# FPGA.net
KiCad netlist of a schematic drawn in Altium Designer
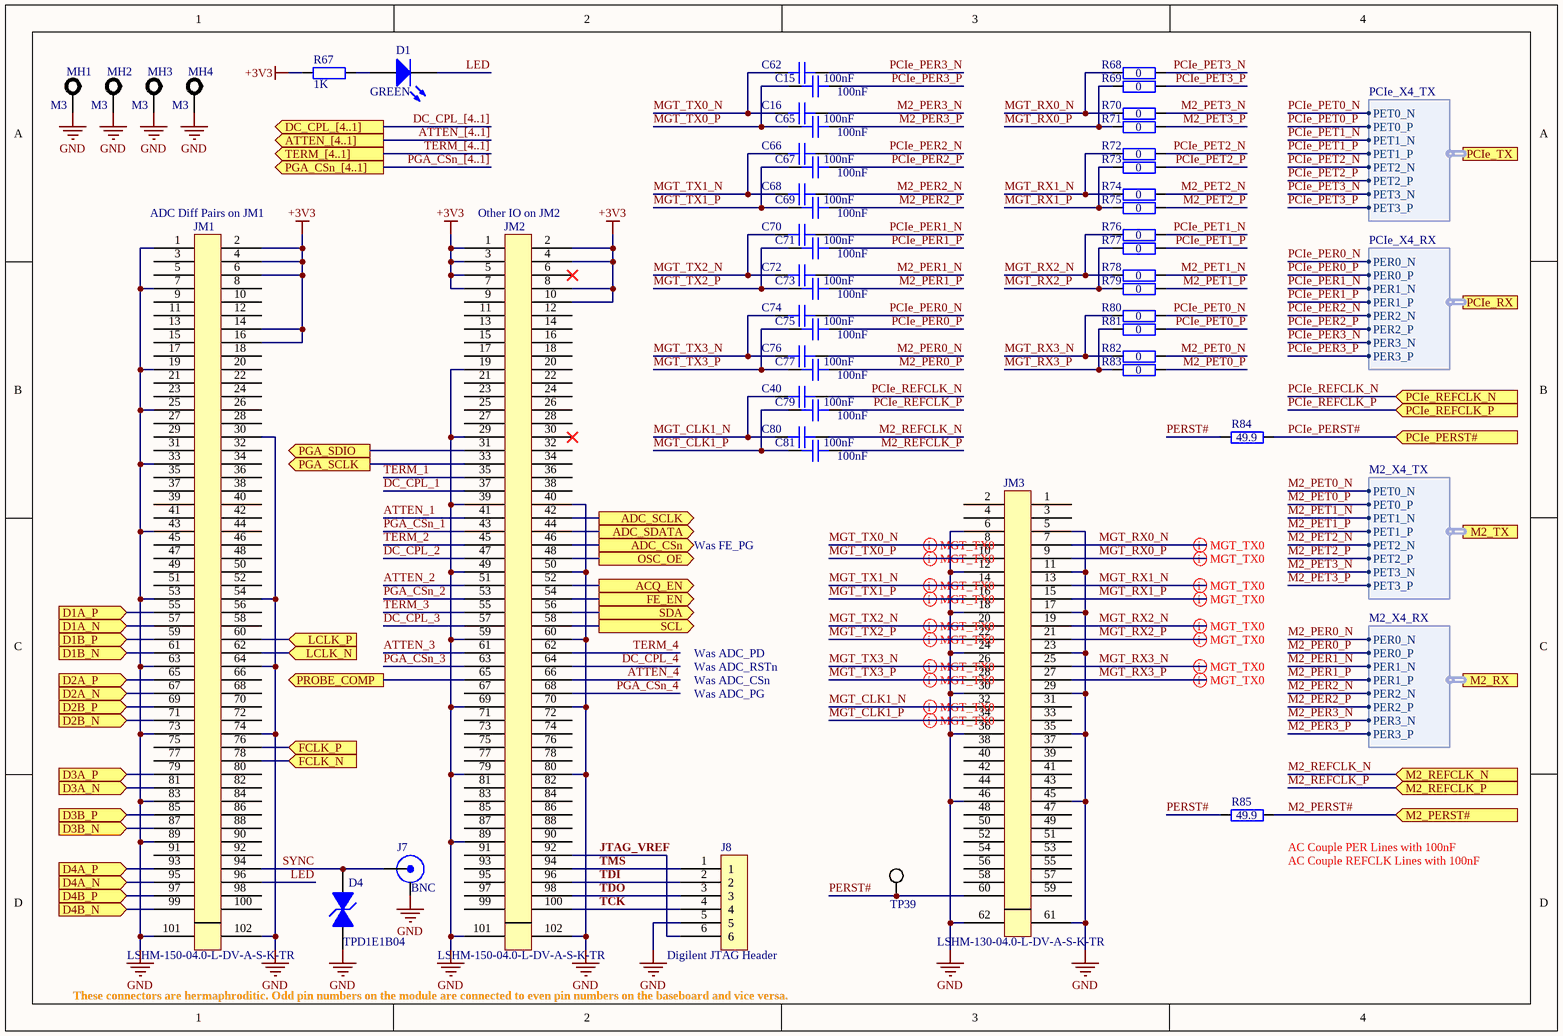
[diagram p0: FPGA.SchDoc]

(export (version "E")
  (design (tool "Eeschema 10.0.6"))
  (components
    (comp (ref "C15")
      (value "100nF")
      (footprint "GEN_C_0201")
      (libsource (lib "DSO") (part "CAP 100nF 6.3V X5R 0201"))
    )
    (comp (ref "C16")
      (value "100nF")
      (footprint "GEN_C_0201")
      (libsource (lib "DSO") (part "CAP 100nF 6.3V X5R 0201"))
    )
    (comp (ref "C40")
      (value "100nF")
      (footprint "GEN_C_0201")
      (libsource (lib "DSO") (part "CAP 100nF 6.3V X5R 0201"))
    )
    (comp (ref "C62")
      (value "100nF")
      (footprint "GEN_C_0201")
      (libsource (lib "DSO") (part "CAP 100nF 6.3V X5R 0201"))
    )
    (comp (ref "C65")
      (value "100nF")
      (footprint "GEN_C_0201")
      (libsource (lib "DSO") (part "CAP 100nF 6.3V X5R 0201"))
    )
    (comp (ref "C66")
      (value "100nF")
      (footprint "GEN_C_0201")
      (libsource (lib "DSO") (part "CAP 100nF 6.3V X5R 0201"))
    )
    (comp (ref "C67")
      (value "100nF")
      (footprint "GEN_C_0201")
      (libsource (lib "DSO") (part "CAP 100nF 6.3V X5R 0201"))
    )
    (comp (ref "C68")
      (value "100nF")
      (footprint "GEN_C_0201")
      (libsource (lib "DSO") (part "CAP 100nF 6.3V X5R 0201"))
    )
    (comp (ref "C69")
      (value "100nF")
      (footprint "GEN_C_0201")
      (libsource (lib "DSO") (part "CAP 100nF 6.3V X5R 0201"))
    )
    (comp (ref "C70")
      (value "100nF")
      (footprint "GEN_C_0201")
      (libsource (lib "DSO") (part "CAP 100nF 6.3V X5R 0201"))
    )
    (comp (ref "C71")
      (value "100nF")
      (footprint "GEN_C_0201")
      (libsource (lib "DSO") (part "CAP 100nF 6.3V X5R 0201"))
    )
    (comp (ref "C72")
      (value "100nF")
      (footprint "GEN_C_0201")
      (libsource (lib "DSO") (part "CAP 100nF 6.3V X5R 0201"))
    )
    (comp (ref "C73")
      (value "100nF")
      (footprint "GEN_C_0201")
      (libsource (lib "DSO") (part "CAP 100nF 6.3V X5R 0201"))
    )
    (comp (ref "C74")
      (value "100nF")
      (footprint "GEN_C_0201")
      (libsource (lib "DSO") (part "CAP 100nF 6.3V X5R 0201"))
    )
    (comp (ref "C75")
      (value "100nF")
      (footprint "GEN_C_0201")
      (libsource (lib "DSO") (part "CAP 100nF 6.3V X5R 0201"))
    )
    (comp (ref "C76")
      (value "100nF")
      (footprint "GEN_C_0201")
      (libsource (lib "DSO") (part "CAP 100nF 6.3V X5R 0201"))
    )
    (comp (ref "C77")
      (value "100nF")
      (footprint "GEN_C_0201")
      (libsource (lib "DSO") (part "CAP 100nF 6.3V X5R 0201"))
    )
    (comp (ref "C79")
      (value "100nF")
      (footprint "GEN_C_0201")
      (libsource (lib "DSO") (part "CAP 100nF 6.3V X5R 0201"))
    )
    (comp (ref "C80")
      (value "100nF")
      (footprint "GEN_C_0201")
      (libsource (lib "DSO") (part "CAP 100nF 6.3V X5R 0201"))
    )
    (comp (ref "C81")
      (value "100nF")
      (footprint "GEN_C_0201")
      (libsource (lib "DSO") (part "CAP 100nF 6.3V X5R 0201"))
    )
    (comp (ref "D1")
      (value "GREEN")
      (footprint "LED_0603_LTST-S270K")
      (libsource (lib "DSO") (part "LED GREEN 0603 LTST-S270K"))
    )
    (comp (ref "D4")
      (value "TPD1E1B04")
      (footprint "TI_X1SON_DPY0002A")
      (libsource (lib "DSO") (part "TVS TPD1E1B04"))
    )
    (comp (ref "J7") (value "BNC") (footprint "MOL_0731000105") (libsource (lib "DSO") (part "BNC JACK R/A")))
    (comp (ref "J8")
      (value "2.54mm 6 Pin TH")
      (footprint "GEN_2.54mm_6_Pin_TH_RA")
      (libsource (lib "DSO") (part "CONN 2.54mm 6 Pin TH RA"))
    )
    (comp (ref "JM1")
      (value "LSHM-150-04.0-L-DV-A-S-K-TR")
      (footprint "SAM_LSHM-150-XX.X-XX-DV-A-S")
      (libsource (lib "DSO") (part "CONN LSHM-150-04.0-L-DV-A-S-K-TR"))
    )
    (comp (ref "JM2")
      (value "LSHM-150-04.0-L-DV-A-S-K-TR")
      (footprint "SAM_LSHM-150-XX.X-XX-DV-A-S")
      (libsource (lib "DSO") (part "CONN LSHM-150-04.0-L-DV-A-S-K-TR"))
    )
    (comp (ref "JM3")
      (value "LSHM-130-04.0-L-DV-A-S-K-TR")
      (footprint "SAM_LSHM-130-XX.X-XX-DV-A-S")
      (libsource (lib "DSO") (part "CONN LSHM-130-04.0-L-DV-A-S-K-TR"))
    )
    (comp (ref "MH1") (value "M3") (footprint "MH M3") (libsource (lib "DSO") (part "MH M3")))
    (comp (ref "MH2") (value "M3") (footprint "MH M3") (libsource (lib "DSO") (part "MH M3")))
    (comp (ref "MH3") (value "M3") (footprint "MH M3") (libsource (lib "DSO") (part "MH M3")))
    (comp (ref "MH4") (value "M3") (footprint "MH M3") (libsource (lib "DSO") (part "MH M3")))
    (comp (ref "R67")
      (value "1K")
      (footprint "GEN_R_0402")
      (fields (field (name "TOLERANCE") "1%"))
      (libsource (lib "DSO") (part "RES 1K OHM 1% 1/10W 0402"))
    )
    (comp (ref "R68")
      (value "0")
      (footprint "GEN_R_0201")
      (fields (field (name "TOLERANCE") "1%"))
      (libsource (lib "DSO") (part "RES 0 OHM 1% 1/20W 0201"))
    )
    (comp (ref "R69")
      (value "0")
      (footprint "GEN_R_0201")
      (fields (field (name "TOLERANCE") "1%"))
      (libsource (lib "DSO") (part "RES 0 OHM 1% 1/20W 0201"))
    )
    (comp (ref "R70")
      (value "0")
      (footprint "GEN_R_0201")
      (fields (field (name "TOLERANCE") "1%"))
      (libsource (lib "DSO") (part "RES 0 OHM 1% 1/20W 0201"))
    )
    (comp (ref "R71")
      (value "0")
      (footprint "GEN_R_0201")
      (fields (field (name "TOLERANCE") "1%"))
      (libsource (lib "DSO") (part "RES 0 OHM 1% 1/20W 0201"))
    )
    (comp (ref "R72")
      (value "0")
      (footprint "GEN_R_0201")
      (fields (field (name "TOLERANCE") "1%"))
      (libsource (lib "DSO") (part "RES 0 OHM 1% 1/20W 0201"))
    )
    (comp (ref "R73")
      (value "0")
      (footprint "GEN_R_0201")
      (fields (field (name "TOLERANCE") "1%"))
      (libsource (lib "DSO") (part "RES 0 OHM 1% 1/20W 0201"))
    )
    (comp (ref "R74")
      (value "0")
      (footprint "GEN_R_0201")
      (fields (field (name "TOLERANCE") "1%"))
      (libsource (lib "DSO") (part "RES 0 OHM 1% 1/20W 0201"))
    )
    (comp (ref "R75")
      (value "0")
      (footprint "GEN_R_0201")
      (fields (field (name "TOLERANCE") "1%"))
      (libsource (lib "DSO") (part "RES 0 OHM 1% 1/20W 0201"))
    )
    (comp (ref "R76")
      (value "0")
      (footprint "GEN_R_0201")
      (fields (field (name "TOLERANCE") "1%"))
      (libsource (lib "DSO") (part "RES 0 OHM 1% 1/20W 0201"))
    )
    (comp (ref "R77")
      (value "0")
      (footprint "GEN_R_0201")
      (fields (field (name "TOLERANCE") "1%"))
      (libsource (lib "DSO") (part "RES 0 OHM 1% 1/20W 0201"))
    )
    (comp (ref "R78")
      (value "0")
      (footprint "GEN_R_0201")
      (fields (field (name "TOLERANCE") "1%"))
      (libsource (lib "DSO") (part "RES 0 OHM 1% 1/20W 0201"))
    )
    (comp (ref "R79")
      (value "0")
      (footprint "GEN_R_0201")
      (fields (field (name "TOLERANCE") "1%"))
      (libsource (lib "DSO") (part "RES 0 OHM 1% 1/20W 0201"))
    )
    (comp (ref "R80")
      (value "0")
      (footprint "GEN_R_0201")
      (fields (field (name "TOLERANCE") "1%"))
      (libsource (lib "DSO") (part "RES 0 OHM 1% 1/20W 0201"))
    )
    (comp (ref "R81")
      (value "0")
      (footprint "GEN_R_0201")
      (fields (field (name "TOLERANCE") "1%"))
      (libsource (lib "DSO") (part "RES 0 OHM 1% 1/20W 0201"))
    )
    (comp (ref "R82")
      (value "0")
      (footprint "GEN_R_0201")
      (fields (field (name "TOLERANCE") "1%"))
      (libsource (lib "DSO") (part "RES 0 OHM 1% 1/20W 0201"))
    )
    (comp (ref "R83")
      (value "0")
      (footprint "GEN_R_0201")
      (fields (field (name "TOLERANCE") "1%"))
      (libsource (lib "DSO") (part "RES 0 OHM 1% 1/20W 0201"))
    )
    (comp (ref "R84")
      (value "49.9")
      (footprint "GEN_R_0402")
      (fields (field (name "TOLERANCE") "1%"))
      (libsource (lib "DSO") (part "RES 49.9 OHM 1% 1/10W 0402"))
    )
    (comp (ref "R85")
      (value "49.9")
      (footprint "GEN_R_0402")
      (fields (field (name "TOLERANCE") "1%"))
      (libsource (lib "DSO") (part "RES 49.9 OHM 1% 1/10W 0402"))
    )
    (comp (ref "TP39") (value "PCB") (footprint "GEN_TP_PCB") (libsource (lib "DSO") (part "TP PCB 1mm")))
  )
  (nets
    (net (code "5") (name "+3V3") (class "Default")
      (node (ref "JM1") (pin "14") (pinfunction "14_14") (pintype "passive"))
      (node (ref "JM1") (pin "16") (pinfunction "16_16") (pintype "passive"))
      (node (ref "JM1") (pin "2") (pinfunction "2_2") (pintype "passive"))
      (node (ref "JM1") (pin "4") (pinfunction "4_4") (pintype "passive"))
      (node (ref "JM1") (pin "6") (pinfunction "6_6") (pintype "passive"))
      (node (ref "JM2") (pin "1") (pinfunction "1_1") (pintype "passive"))
      (node (ref "JM2") (pin "10") (pinfunction "10_10") (pintype "passive"))
      (node (ref "JM2") (pin "2") (pinfunction "2_2") (pintype "passive"))
      (node (ref "JM2") (pin "3") (pinfunction "3_3") (pintype "passive"))
      (node (ref "JM2") (pin "4") (pinfunction "4_4") (pintype "passive"))
      (node (ref "JM2") (pin "5") (pinfunction "5_5") (pintype "passive"))
      (node (ref "JM2") (pin "7") (pinfunction "7_7") (pintype "passive"))
      (node (ref "JM2") (pin "8") (pinfunction "8_8") (pintype "passive"))
      (node (ref "R67") (pin "2") (pinfunction "2_2") (pintype "passive"))
    )
    (net (code "6") (name "/ACQ_EN") (class "Default")
      (node (ref "JM2") (pin "52") (pinfunction "52_52") (pintype "passive"))
    )
    (net (code "7") (name "/ADC_CSn") (class "Default")
      (node (ref "JM2") (pin "46") (pinfunction "46_46") (pintype "passive"))
    )
    (net (code "8") (name "/ADC_SCLK") (class "Default")
      (node (ref "JM2") (pin "42") (pinfunction "42_42") (pintype "passive"))
    )
    (net (code "9") (name "/ADC_SDATA") (class "Default")
      (node (ref "JM2") (pin "44") (pinfunction "44_44") (pintype "passive"))
    )
    (net (code "10") (name "/ATTEN_1") (class "Default")
      (node (ref "JM2") (pin "41") (pinfunction "41_41") (pintype "passive"))
    )
    (net (code "11") (name "/ATTEN_2") (class "Default")
      (node (ref "JM2") (pin "51") (pinfunction "51_51") (pintype "passive"))
    )
    (net (code "12") (name "/ATTEN_3") (class "Default")
      (node (ref "JM2") (pin "61") (pinfunction "61_61") (pintype "passive"))
    )
    (net (code "13") (name "/ATTEN_4") (class "Default")
      (node (ref "JM2") (pin "66") (pinfunction "66_66") (pintype "passive"))
    )
    (net (code "15") (name "/D1A_N") (class "Default")
      (node (ref "JM1") (pin "57") (pinfunction "57_57") (pintype "passive"))
    )
    (net (code "16") (name "/D1A_P") (class "Default")
      (node (ref "JM1") (pin "55") (pinfunction "55_55") (pintype "passive"))
    )
    (net (code "17") (name "/D1B_N") (class "Default")
      (node (ref "JM1") (pin "61") (pinfunction "61_61") (pintype "passive"))
    )
    (net (code "18") (name "/D1B_P") (class "Default")
      (node (ref "JM1") (pin "59") (pinfunction "59_59") (pintype "passive"))
    )
    (net (code "19") (name "/D2A_N") (class "Default")
      (node (ref "JM1") (pin "67") (pinfunction "67_67") (pintype "passive"))
    )
    (net (code "20") (name "/D2A_P") (class "Default")
      (node (ref "JM1") (pin "65") (pinfunction "65_65") (pintype "passive"))
    )
    (net (code "21") (name "/D2B_N") (class "Default")
      (node (ref "JM1") (pin "71") (pinfunction "71_71") (pintype "passive"))
    )
    (net (code "22") (name "/D2B_P") (class "Default")
      (node (ref "JM1") (pin "69") (pinfunction "69_69") (pintype "passive"))
    )
    (net (code "23") (name "/D3A_N") (class "Default")
      (node (ref "JM1") (pin "81") (pinfunction "81_81") (pintype "passive"))
    )
    (net (code "24") (name "/D3A_P") (class "Default")
      (node (ref "JM1") (pin "79") (pinfunction "79_79") (pintype "passive"))
    )
    (net (code "25") (name "/D3B_N") (class "Default")
      (node (ref "JM1") (pin "87") (pinfunction "87_87") (pintype "passive"))
    )
    (net (code "26") (name "/D3B_P") (class "Default")
      (node (ref "JM1") (pin "85") (pinfunction "85_85") (pintype "passive"))
    )
    (net (code "27") (name "/D4A_N") (class "Default")
      (node (ref "JM1") (pin "95") (pinfunction "95_95") (pintype "passive"))
    )
    (net (code "28") (name "/D4A_P") (class "Default")
      (node (ref "JM1") (pin "93") (pinfunction "93_93") (pintype "passive"))
    )
    (net (code "29") (name "/D4B_N") (class "Default")
      (node (ref "JM1") (pin "99") (pinfunction "99_99") (pintype "passive"))
    )
    (net (code "30") (name "/D4B_P") (class "Default")
      (node (ref "JM1") (pin "97") (pinfunction "97_97") (pintype "passive"))
    )
    (net (code "31") (name "/DC_CPL_1") (class "Default")
      (node (ref "JM2") (pin "37") (pinfunction "37_37") (pintype "passive"))
    )
    (net (code "32") (name "/DC_CPL_2") (class "Default")
      (node (ref "JM2") (pin "47") (pinfunction "47_47") (pintype "passive"))
    )
    (net (code "33") (name "/DC_CPL_3") (class "Default")
      (node (ref "JM2") (pin "57") (pinfunction "57_57") (pintype "passive"))
    )
    (net (code "34") (name "/DC_CPL_4") (class "Default")
      (node (ref "JM2") (pin "64") (pinfunction "64_64") (pintype "passive"))
    )
    (net (code "36") (name "/FCLK_N") (class "Default")
      (node (ref "JM1") (pin "78") (pinfunction "78_78") (pintype "passive"))
    )
    (net (code "37") (name "/FCLK_P") (class "Default")
      (node (ref "JM1") (pin "76") (pinfunction "76_76") (pintype "passive"))
    )
    (net (code "38") (name "/FE_EN") (class "Default")
      (node (ref "JM2") (pin "54") (pinfunction "54_54") (pintype "passive"))
    )
    (net (code "39") (name "/JTAG_VREF") (class "Default")
      (node (ref "J8") (pin "6") (pinfunction "6_6") (pintype "passive"))
      (node (ref "JM2") (pin "92") (pinfunction "92_92") (pintype "passive"))
    )
    (net (code "40") (name "/LCLK_N") (class "Default")
      (node (ref "JM1") (pin "62") (pinfunction "62_62") (pintype "passive"))
    )
    (net (code "41") (name "/LCLK_P") (class "Default")
      (node (ref "JM1") (pin "60") (pinfunction "60_60") (pintype "passive"))
    )
    (net (code "42") (name "/LED") (class "Default")
      (node (ref "D1") (pin "1") (pinfunction "K_1") (pintype "passive"))
      (node (ref "JM1") (pin "96") (pinfunction "96_96") (pintype "passive"))
    )
    (net (code "43") (name "/M2_PER0_N") (class "Default")
      (node (ref "C76") (pin "1") (pinfunction "1_1") (pintype "passive"))
    )
    (net (code "44") (name "/M2_PER0_P") (class "Default")
      (node (ref "C77") (pin "1") (pinfunction "1_1") (pintype "passive"))
    )
    (net (code "45") (name "/M2_PER1_N") (class "Default")
      (node (ref "C72") (pin "1") (pinfunction "1_1") (pintype "passive"))
    )
    (net (code "46") (name "/M2_PER1_P") (class "Default")
      (node (ref "C73") (pin "1") (pinfunction "1_1") (pintype "passive"))
    )
    (net (code "47") (name "/M2_PER2_N") (class "Default")
      (node (ref "C68") (pin "1") (pinfunction "1_1") (pintype "passive"))
    )
    (net (code "48") (name "/M2_PER2_P") (class "Default")
      (node (ref "C69") (pin "1") (pinfunction "1_1") (pintype "passive"))
    )
    (net (code "49") (name "/M2_PER3_N") (class "Default")
      (node (ref "C16") (pin "1") (pinfunction "1_1") (pintype "passive"))
    )
    (net (code "50") (name "/M2_PER3_P") (class "Default")
      (node (ref "C65") (pin "1") (pinfunction "1_1") (pintype "passive"))
    )
    (net (code "51") (name "/M2_PERST#") (class "Default")
      (node (ref "R85") (pin "2") (pinfunction "2_2") (pintype "passive"))
    )
    (net (code "52") (name "/M2_PET0_N") (class "Default")
      (node (ref "R82") (pin "2") (pinfunction "2_2") (pintype "passive"))
    )
    (net (code "53") (name "/M2_PET0_P") (class "Default")
      (node (ref "R83") (pin "2") (pinfunction "2_2") (pintype "passive"))
    )
    (net (code "54") (name "/M2_PET1_N") (class "Default")
      (node (ref "R78") (pin "2") (pinfunction "2_2") (pintype "passive"))
    )
    (net (code "55") (name "/M2_PET1_P") (class "Default")
      (node (ref "R79") (pin "2") (pinfunction "2_2") (pintype "passive"))
    )
    (net (code "56") (name "/M2_PET2_N") (class "Default")
      (node (ref "R74") (pin "2") (pinfunction "2_2") (pintype "passive"))
    )
    (net (code "57") (name "/M2_PET2_P") (class "Default")
      (node (ref "R75") (pin "2") (pinfunction "2_2") (pintype "passive"))
    )
    (net (code "58") (name "/M2_PET3_N") (class "Default")
      (node (ref "R70") (pin "2") (pinfunction "2_2") (pintype "passive"))
    )
    (net (code "59") (name "/M2_PET3_P") (class "Default")
      (node (ref "R71") (pin "2") (pinfunction "2_2") (pintype "passive"))
    )
    (net (code "60") (name "/M2_REFCLK_N") (class "Default")
      (node (ref "C80") (pin "1") (pinfunction "1_1") (pintype "passive"))
    )
    (net (code "61") (name "/M2_REFCLK_P") (class "Default")
      (node (ref "C81") (pin "1") (pinfunction "1_1") (pintype "passive"))
    )
    (net (code "62") (name "/MGT_CLK1_N") (class "Default")
      (node (ref "C40") (pin "2") (pinfunction "2_2") (pintype "passive"))
      (node (ref "C80") (pin "2") (pinfunction "2_2") (pintype "passive"))
      (node (ref "JM3") (pin "32") (pinfunction "32_32") (pintype "passive"))
    )
    (net (code "63") (name "/MGT_CLK1_P") (class "Default")
      (node (ref "C79") (pin "2") (pinfunction "2_2") (pintype "passive"))
      (node (ref "C81") (pin "2") (pinfunction "2_2") (pintype "passive"))
      (node (ref "JM3") (pin "34") (pinfunction "34_34") (pintype "passive"))
    )
    (net (code "64") (name "/MGT_RX0_N") (class "Default")
      (node (ref "JM3") (pin "7") (pinfunction "7_7") (pintype "passive"))
      (node (ref "R68") (pin "1") (pinfunction "1_1") (pintype "passive"))
      (node (ref "R70") (pin "1") (pinfunction "1_1") (pintype "passive"))
    )
    (net (code "65") (name "/MGT_RX0_P") (class "Default")
      (node (ref "JM3") (pin "9") (pinfunction "9_9") (pintype "passive"))
      (node (ref "R69") (pin "1") (pinfunction "1_1") (pintype "passive"))
      (node (ref "R71") (pin "1") (pinfunction "1_1") (pintype "passive"))
    )
    (net (code "66") (name "/MGT_RX1_N") (class "Default")
      (node (ref "JM3") (pin "13") (pinfunction "13_13") (pintype "passive"))
      (node (ref "R72") (pin "1") (pinfunction "1_1") (pintype "passive"))
      (node (ref "R74") (pin "1") (pinfunction "1_1") (pintype "passive"))
    )
    (net (code "67") (name "/MGT_RX1_P") (class "Default")
      (node (ref "JM3") (pin "15") (pinfunction "15_15") (pintype "passive"))
      (node (ref "R73") (pin "1") (pinfunction "1_1") (pintype "passive"))
      (node (ref "R75") (pin "1") (pinfunction "1_1") (pintype "passive"))
    )
    (net (code "68") (name "/MGT_RX2_N") (class "Default")
      (node (ref "JM3") (pin "19") (pinfunction "19_19") (pintype "passive"))
      (node (ref "R76") (pin "1") (pinfunction "1_1") (pintype "passive"))
      (node (ref "R78") (pin "1") (pinfunction "1_1") (pintype "passive"))
    )
    (net (code "69") (name "/MGT_RX2_P") (class "Default")
      (node (ref "JM3") (pin "21") (pinfunction "21_21") (pintype "passive"))
      (node (ref "R77") (pin "1") (pinfunction "1_1") (pintype "passive"))
      (node (ref "R79") (pin "1") (pinfunction "1_1") (pintype "passive"))
    )
    (net (code "70") (name "/MGT_RX3_N") (class "Default")
      (node (ref "JM3") (pin "25") (pinfunction "25_25") (pintype "passive"))
      (node (ref "R80") (pin "1") (pinfunction "1_1") (pintype "passive"))
      (node (ref "R82") (pin "1") (pinfunction "1_1") (pintype "passive"))
    )
    (net (code "71") (name "/MGT_RX3_P") (class "Default")
      (node (ref "JM3") (pin "27") (pinfunction "27_27") (pintype "passive"))
      (node (ref "R81") (pin "1") (pinfunction "1_1") (pintype "passive"))
      (node (ref "R83") (pin "1") (pinfunction "1_1") (pintype "passive"))
    )
    (net (code "72") (name "/MGT_TX0_N") (class "Default")
      (node (ref "C16") (pin "2") (pinfunction "2_2") (pintype "passive"))
      (node (ref "C62") (pin "2") (pinfunction "2_2") (pintype "passive"))
      (node (ref "JM3") (pin "8") (pinfunction "8_8") (pintype "passive"))
    )
    (net (code "73") (name "/MGT_TX0_P") (class "Default")
      (node (ref "C15") (pin "2") (pinfunction "2_2") (pintype "passive"))
      (node (ref "C65") (pin "2") (pinfunction "2_2") (pintype "passive"))
      (node (ref "JM3") (pin "10") (pinfunction "10_10") (pintype "passive"))
    )
    (net (code "74") (name "/MGT_TX1_N") (class "Default")
      (node (ref "C66") (pin "2") (pinfunction "2_2") (pintype "passive"))
      (node (ref "C68") (pin "2") (pinfunction "2_2") (pintype "passive"))
      (node (ref "JM3") (pin "14") (pinfunction "14_14") (pintype "passive"))
    )
    (net (code "75") (name "/MGT_TX1_P") (class "Default")
      (node (ref "C67") (pin "2") (pinfunction "2_2") (pintype "passive"))
      (node (ref "C69") (pin "2") (pinfunction "2_2") (pintype "passive"))
      (node (ref "JM3") (pin "16") (pinfunction "16_16") (pintype "passive"))
    )
    (net (code "76") (name "/MGT_TX2_N") (class "Default")
      (node (ref "C70") (pin "2") (pinfunction "2_2") (pintype "passive"))
      (node (ref "C72") (pin "2") (pinfunction "2_2") (pintype "passive"))
      (node (ref "JM3") (pin "20") (pinfunction "20_20") (pintype "passive"))
    )
    (net (code "77") (name "/MGT_TX2_P") (class "Default")
      (node (ref "C71") (pin "2") (pinfunction "2_2") (pintype "passive"))
      (node (ref "C73") (pin "2") (pinfunction "2_2") (pintype "passive"))
      (node (ref "JM3") (pin "22") (pinfunction "22_22") (pintype "passive"))
    )
    (net (code "78") (name "/MGT_TX3_N") (class "Default")
      (node (ref "C74") (pin "2") (pinfunction "2_2") (pintype "passive"))
      (node (ref "C76") (pin "2") (pinfunction "2_2") (pintype "passive"))
      (node (ref "JM3") (pin "26") (pinfunction "26_26") (pintype "passive"))
    )
    (net (code "79") (name "/MGT_TX3_P") (class "Default")
      (node (ref "C75") (pin "2") (pinfunction "2_2") (pintype "passive"))
      (node (ref "C77") (pin "2") (pinfunction "2_2") (pintype "passive"))
      (node (ref "JM3") (pin "28") (pinfunction "28_28") (pintype "passive"))
    )
    (net (code "80") (name "/OSC_OE") (class "Default")
      (node (ref "JM2") (pin "48") (pinfunction "48_48") (pintype "passive"))
    )
    (net (code "81") (name "/PCIe_PER0_N") (class "Default")
      (node (ref "C74") (pin "1") (pinfunction "1_1") (pintype "passive"))
    )
    (net (code "82") (name "/PCIe_PER0_P") (class "Default")
      (node (ref "C75") (pin "1") (pinfunction "1_1") (pintype "passive"))
    )
    (net (code "83") (name "/PCIe_PER1_N") (class "Default")
      (node (ref "C70") (pin "1") (pinfunction "1_1") (pintype "passive"))
    )
    (net (code "84") (name "/PCIe_PER1_P") (class "Default")
      (node (ref "C71") (pin "1") (pinfunction "1_1") (pintype "passive"))
    )
    (net (code "85") (name "/PCIe_PER2_N") (class "Default")
      (node (ref "C66") (pin "1") (pinfunction "1_1") (pintype "passive"))
    )
    (net (code "86") (name "/PCIe_PER2_P") (class "Default")
      (node (ref "C67") (pin "1") (pinfunction "1_1") (pintype "passive"))
    )
    (net (code "87") (name "/PCIe_PER3_N") (class "Default")
      (node (ref "C62") (pin "1") (pinfunction "1_1") (pintype "passive"))
    )
    (net (code "88") (name "/PCIe_PER3_P") (class "Default")
      (node (ref "C15") (pin "1") (pinfunction "1_1") (pintype "passive"))
    )
    (net (code "89") (name "/PCIe_PERST#") (class "Default")
      (node (ref "R84") (pin "2") (pinfunction "2_2") (pintype "passive"))
    )
    (net (code "90") (name "/PCIe_PET0_N") (class "Default")
      (node (ref "R80") (pin "2") (pinfunction "2_2") (pintype "passive"))
    )
    (net (code "91") (name "/PCIe_PET0_P") (class "Default")
      (node (ref "R81") (pin "2") (pinfunction "2_2") (pintype "passive"))
    )
    (net (code "92") (name "/PCIe_PET1_N") (class "Default")
      (node (ref "R76") (pin "2") (pinfunction "2_2") (pintype "passive"))
    )
    (net (code "93") (name "/PCIe_PET1_P") (class "Default")
      (node (ref "R77") (pin "2") (pinfunction "2_2") (pintype "passive"))
    )
    (net (code "94") (name "/PCIe_PET2_N") (class "Default")
      (node (ref "R72") (pin "2") (pinfunction "2_2") (pintype "passive"))
    )
    (net (code "95") (name "/PCIe_PET2_P") (class "Default")
      (node (ref "R73") (pin "2") (pinfunction "2_2") (pintype "passive"))
    )
    (net (code "96") (name "/PCIe_PET3_N") (class "Default")
      (node (ref "R68") (pin "2") (pinfunction "2_2") (pintype "passive"))
    )
    (net (code "97") (name "/PCIe_PET3_P") (class "Default")
      (node (ref "R69") (pin "2") (pinfunction "2_2") (pintype "passive"))
    )
    (net (code "98") (name "/PCIe_REFCLK_N") (class "Default")
      (node (ref "C40") (pin "1") (pinfunction "1_1") (pintype "passive"))
    )
    (net (code "99") (name "/PCIe_REFCLK_P") (class "Default")
      (node (ref "C79") (pin "1") (pinfunction "1_1") (pintype "passive"))
    )
    (net (code "100") (name "/PERST#") (class "Default")
      (node (ref "JM3") (pin "60") (pinfunction "60_60") (pintype "passive"))
      (node (ref "R84") (pin "1") (pinfunction "1_1") (pintype "passive"))
      (node (ref "R85") (pin "1") (pinfunction "1_1") (pintype "passive"))
      (node (ref "TP39") (pin "1") (pinfunction "1_1") (pintype "passive"))
    )
    (net (code "101") (name "/PGA_CSn_1") (class "Default")
      (node (ref "JM2") (pin "43") (pinfunction "43_43") (pintype "passive"))
    )
    (net (code "102") (name "/PGA_CSn_2") (class "Default")
      (node (ref "JM2") (pin "53") (pinfunction "53_53") (pintype "passive"))
    )
    (net (code "103") (name "/PGA_CSn_3") (class "Default")
      (node (ref "JM2") (pin "63") (pinfunction "63_63") (pintype "passive"))
    )
    (net (code "104") (name "/PGA_CSn_4") (class "Default")
      (node (ref "JM2") (pin "68") (pinfunction "68_68") (pintype "passive"))
    )
    (net (code "106") (name "/PGA_SCLK") (class "Default")
      (node (ref "JM2") (pin "33") (pinfunction "33_33") (pintype "passive"))
    )
    (net (code "107") (name "/PGA_SDIO") (class "Default")
      (node (ref "JM2") (pin "31") (pinfunction "31_31") (pintype "passive"))
    )
    (net (code "108") (name "/PROBE_COMP") (class "Default")
      (node (ref "JM2") (pin "65") (pinfunction "65_65") (pintype "passive"))
    )
    (net (code "109") (name "/SCL") (class "Default")
      (node (ref "JM2") (pin "58") (pinfunction "58_58") (pintype "passive"))
    )
    (net (code "110") (name "/SDA") (class "Default")
      (node (ref "JM2") (pin "56") (pinfunction "56_56") (pintype "passive"))
    )
    (net (code "111") (name "/SYNC") (class "Default")
      (node (ref "D4") (pin "1") (pinfunction "K_1") (pintype "passive"))
      (node (ref "J7") (pin "1") (pinfunction "Signal_1") (pintype "passive"))
      (node (ref "JM1") (pin "94") (pinfunction "94_94") (pintype "passive"))
    )
    (net (code "112") (name "/TCK") (class "Default")
      (node (ref "J8") (pin "4") (pinfunction "4_4") (pintype "passive"))
      (node (ref "JM2") (pin "100") (pinfunction "100_100") (pintype "passive"))
    )
    (net (code "113") (name "/TDI") (class "Default")
      (node (ref "J8") (pin "2") (pinfunction "2_2") (pintype "passive"))
      (node (ref "JM2") (pin "96") (pinfunction "96_96") (pintype "passive"))
    )
    (net (code "114") (name "/TDO") (class "Default")
      (node (ref "J8") (pin "3") (pinfunction "3_3") (pintype "passive"))
      (node (ref "JM2") (pin "98") (pinfunction "98_98") (pintype "passive"))
    )
    (net (code "115") (name "/TERM_1") (class "Default")
      (node (ref "JM2") (pin "35") (pinfunction "35_35") (pintype "passive"))
    )
    (net (code "116") (name "/TERM_2") (class "Default")
      (node (ref "JM2") (pin "45") (pinfunction "45_45") (pintype "passive"))
    )
    (net (code "117") (name "/TERM_3") (class "Default")
      (node (ref "JM2") (pin "55") (pinfunction "55_55") (pintype "passive"))
    )
    (net (code "118") (name "/TERM_4") (class "Default")
      (node (ref "JM2") (pin "62") (pinfunction "62_62") (pintype "passive"))
    )
    (net (code "120") (name "/TMS") (class "Default")
      (node (ref "J8") (pin "1") (pinfunction "1_1") (pintype "passive"))
      (node (ref "JM2") (pin "94") (pinfunction "94_94") (pintype "passive"))
    )
    (net (code "125") (name "GND") (class "Default")
      (node (ref "D4") (pin "2") (pinfunction "A_2") (pintype "passive"))
      (node (ref "J7") (pin "2") (pinfunction "SHIELD_2") (pintype "passive"))
      (node (ref "J8") (pin "5") (pinfunction "5_5") (pintype "passive"))
      (node (ref "JM1") (pin "1") (pinfunction "1_1") (pintype "passive"))
      (node (ref "JM1") (pin "101") (pinfunction "101_101") (pintype "passive"))
      (node (ref "JM1") (pin "102") (pinfunction "102_102") (pintype "passive"))
      (node (ref "JM1") (pin "19") (pinfunction "19_19") (pintype "passive"))
      (node (ref "JM1") (pin "25") (pinfunction "25_25") (pintype "passive"))
      (node (ref "JM1") (pin "30") (pinfunction "30_30") (pintype "passive"))
      (node (ref "JM1") (pin "33") (pinfunction "33_33") (pintype "passive"))
      (node (ref "JM1") (pin "43") (pinfunction "43_43") (pintype "passive"))
      (node (ref "JM1") (pin "53") (pinfunction "53_53") (pintype "passive"))
      (node (ref "JM1") (pin "54") (pinfunction "54_54") (pintype "passive"))
      (node (ref "JM1") (pin "63") (pinfunction "63_63") (pintype "passive"))
      (node (ref "JM1") (pin "64") (pinfunction "64_64") (pintype "passive"))
      (node (ref "JM1") (pin "7") (pinfunction "7_7") (pintype "passive"))
      (node (ref "JM1") (pin "73") (pinfunction "73_73") (pintype "passive"))
      (node (ref "JM1") (pin "74") (pinfunction "74_74") (pintype "passive"))
      (node (ref "JM1") (pin "83") (pinfunction "83_83") (pintype "passive"))
      (node (ref "JM1") (pin "89") (pinfunction "89_89") (pintype "passive"))
      (node (ref "JM2") (pin "101") (pinfunction "101_101") (pintype "passive"))
      (node (ref "JM2") (pin "102") (pinfunction "102_102") (pintype "passive"))
      (node (ref "JM2") (pin "19") (pinfunction "19_19") (pintype "passive"))
      (node (ref "JM2") (pin "29") (pinfunction "29_29") (pintype "passive"))
      (node (ref "JM2") (pin "39") (pinfunction "39_39") (pintype "passive"))
      (node (ref "JM2") (pin "40") (pinfunction "40_40") (pintype "passive"))
      (node (ref "JM2") (pin "49") (pinfunction "49_49") (pintype "passive"))
      (node (ref "JM2") (pin "50") (pinfunction "50_50") (pintype "passive"))
      (node (ref "JM2") (pin "59") (pinfunction "59_59") (pintype "passive"))
      (node (ref "JM2") (pin "60") (pinfunction "60_60") (pintype "passive"))
      (node (ref "JM2") (pin "69") (pinfunction "69_69") (pintype "passive"))
      (node (ref "JM2") (pin "70") (pinfunction "70_70") (pintype "passive"))
      (node (ref "JM2") (pin "79") (pinfunction "79_79") (pintype "passive"))
      (node (ref "JM2") (pin "80") (pinfunction "80_80") (pintype "passive"))
      (node (ref "JM2") (pin "89") (pinfunction "89_89") (pintype "passive"))
      (node (ref "JM3") (pin "11") (pinfunction "11_11") (pintype "passive"))
      (node (ref "JM3") (pin "12") (pinfunction "12_12") (pintype "passive"))
      (node (ref "JM3") (pin "17") (pinfunction "17_17") (pintype "passive"))
      (node (ref "JM3") (pin "18") (pinfunction "18_18") (pintype "passive"))
      (node (ref "JM3") (pin "23") (pinfunction "23_23") (pintype "passive"))
      (node (ref "JM3") (pin "24") (pinfunction "24_24") (pintype "passive"))
      (node (ref "JM3") (pin "29") (pinfunction "29_29") (pintype "passive"))
      (node (ref "JM3") (pin "30") (pinfunction "30_30") (pintype "passive"))
      (node (ref "JM3") (pin "35") (pinfunction "35_35") (pintype "passive"))
      (node (ref "JM3") (pin "36") (pinfunction "36_36") (pintype "passive"))
      (node (ref "JM3") (pin "45") (pinfunction "45_45") (pintype "passive"))
      (node (ref "JM3") (pin "46") (pinfunction "46_46") (pintype "passive"))
      (node (ref "JM3") (pin "5") (pinfunction "5_5") (pintype "passive"))
      (node (ref "JM3") (pin "6") (pinfunction "6_6") (pintype "passive"))
      (node (ref "JM3") (pin "61") (pinfunction "61_61") (pintype "passive"))
      (node (ref "JM3") (pin "62") (pinfunction "62_62") (pintype "passive"))
      (node (ref "MH1") (pin "1") (pinfunction "1_1") (pintype "passive"))
      (node (ref "MH2") (pin "1") (pinfunction "1_1") (pintype "passive"))
      (node (ref "MH3") (pin "1") (pinfunction "1_1") (pintype "passive"))
      (node (ref "MH4") (pin "1") (pinfunction "1_1") (pintype "passive"))
    )
    (net (code "126") (name "Net-(D1-A)") (class "Default")
      (node (ref "D1") (pin "2") (pinfunction "A_2") (pintype "passive"))
      (node (ref "R67") (pin "1") (pinfunction "1_1") (pintype "passive"))
    )
    (net (code "127") (name "unconnected-(JM1-Pad3)") (class "Default")
      (node (ref "JM1") (pin "3") (pinfunction "3_3") (pintype "passive"))
    )
    (net (code "128") (name "unconnected-(JM1-Pad5)") (class "Default")
      (node (ref "JM1") (pin "5") (pinfunction "5_5") (pintype "passive"))
    )
    (net (code "129") (name "unconnected-(JM1-Pad8)") (class "Default")
      (node (ref "JM1") (pin "8") (pinfunction "8_8") (pintype "passive"))
    )
    (net (code "130") (name "unconnected-(JM1-Pad9)") (class "Default")
      (node (ref "JM1") (pin "9") (pinfunction "9_9") (pintype "passive"))
    )
    (net (code "131") (name "unconnected-(JM1-Pad10)") (class "Default")
      (node (ref "JM1") (pin "10") (pinfunction "10_10") (pintype "passive"))
    )
    (net (code "132") (name "unconnected-(JM1-Pad11)") (class "Default")
      (node (ref "JM1") (pin "11") (pinfunction "11_11") (pintype "passive"))
    )
    (net (code "133") (name "unconnected-(JM1-Pad12)") (class "Default")
      (node (ref "JM1") (pin "12") (pinfunction "12_12") (pintype "passive"))
    )
    (net (code "134") (name "unconnected-(JM1-Pad13)") (class "Default")
      (node (ref "JM1") (pin "13") (pinfunction "13_13") (pintype "passive"))
    )
    (net (code "135") (name "unconnected-(JM1-Pad15)") (class "Default")
      (node (ref "JM1") (pin "15") (pinfunction "15_15") (pintype "passive"))
    )
    (net (code "136") (name "unconnected-(JM1-Pad17)") (class "Default")
      (node (ref "JM1") (pin "17") (pinfunction "17_17") (pintype "passive"))
    )
    (net (code "137") (name "unconnected-(JM1-Pad18)") (class "Default")
      (node (ref "JM1") (pin "18") (pinfunction "18_18") (pintype "passive"))
    )
    (net (code "138") (name "unconnected-(JM1-Pad20)") (class "Default")
      (node (ref "JM1") (pin "20") (pinfunction "20_20") (pintype "passive"))
    )
    (net (code "139") (name "unconnected-(JM1-Pad21)") (class "Default")
      (node (ref "JM1") (pin "21") (pinfunction "21_21") (pintype "passive"))
    )
    (net (code "140") (name "unconnected-(JM1-Pad22)") (class "Default")
      (node (ref "JM1") (pin "22") (pinfunction "22_22") (pintype "passive"))
    )
    (net (code "141") (name "unconnected-(JM1-Pad23)") (class "Default")
      (node (ref "JM1") (pin "23") (pinfunction "23_23") (pintype "passive"))
    )
    (net (code "142") (name "unconnected-(JM1-Pad24)") (class "Default")
      (node (ref "JM1") (pin "24") (pinfunction "24_24") (pintype "passive"))
    )
    (net (code "143") (name "unconnected-(JM1-Pad26)") (class "Default")
      (node (ref "JM1") (pin "26") (pinfunction "26_26") (pintype "passive"))
    )
    (net (code "144") (name "unconnected-(JM1-Pad27)") (class "Default")
      (node (ref "JM1") (pin "27") (pinfunction "27_27") (pintype "passive"))
    )
    (net (code "145") (name "unconnected-(JM1-Pad28)") (class "Default")
      (node (ref "JM1") (pin "28") (pinfunction "28_28") (pintype "passive"))
    )
    (net (code "146") (name "unconnected-(JM1-Pad29)") (class "Default")
      (node (ref "JM1") (pin "29") (pinfunction "29_29") (pintype "passive"))
    )
    (net (code "147") (name "unconnected-(JM1-Pad31)") (class "Default")
      (node (ref "JM1") (pin "31") (pinfunction "31_31") (pintype "passive"))
    )
    (net (code "148") (name "unconnected-(JM1-Pad32)") (class "Default")
      (node (ref "JM1") (pin "32") (pinfunction "32_32") (pintype "passive"))
    )
    (net (code "149") (name "unconnected-(JM1-Pad34)") (class "Default")
      (node (ref "JM1") (pin "34") (pinfunction "34_34") (pintype "passive"))
    )
    (net (code "150") (name "unconnected-(JM1-Pad35)") (class "Default")
      (node (ref "JM1") (pin "35") (pinfunction "35_35") (pintype "passive"))
    )
    (net (code "151") (name "unconnected-(JM1-Pad36)") (class "Default")
      (node (ref "JM1") (pin "36") (pinfunction "36_36") (pintype "passive"))
    )
    (net (code "152") (name "unconnected-(JM1-Pad37)") (class "Default")
      (node (ref "JM1") (pin "37") (pinfunction "37_37") (pintype "passive"))
    )
    (net (code "153") (name "unconnected-(JM1-Pad38)") (class "Default")
      (node (ref "JM1") (pin "38") (pinfunction "38_38") (pintype "passive"))
    )
    (net (code "154") (name "unconnected-(JM1-Pad39)") (class "Default")
      (node (ref "JM1") (pin "39") (pinfunction "39_39") (pintype "passive"))
    )
    (net (code "155") (name "unconnected-(JM1-Pad40)") (class "Default")
      (node (ref "JM1") (pin "40") (pinfunction "40_40") (pintype "passive"))
    )
    (net (code "156") (name "unconnected-(JM1-Pad41)") (class "Default")
      (node (ref "JM1") (pin "41") (pinfunction "41_41") (pintype "passive"))
    )
    (net (code "157") (name "unconnected-(JM1-Pad42)") (class "Default")
      (node (ref "JM1") (pin "42") (pinfunction "42_42") (pintype "passive"))
    )
    (net (code "158") (name "unconnected-(JM1-Pad44)") (class "Default")
      (node (ref "JM1") (pin "44") (pinfunction "44_44") (pintype "passive"))
    )
    (net (code "159") (name "unconnected-(JM1-Pad45)") (class "Default")
      (node (ref "JM1") (pin "45") (pinfunction "45_45") (pintype "passive"))
    )
    (net (code "160") (name "unconnected-(JM1-Pad46)") (class "Default")
      (node (ref "JM1") (pin "46") (pinfunction "46_46") (pintype "passive"))
    )
    (net (code "161") (name "unconnected-(JM1-Pad47)") (class "Default")
      (node (ref "JM1") (pin "47") (pinfunction "47_47") (pintype "passive"))
    )
    (net (code "162") (name "unconnected-(JM1-Pad48)") (class "Default")
      (node (ref "JM1") (pin "48") (pinfunction "48_48") (pintype "passive"))
    )
    (net (code "163") (name "unconnected-(JM1-Pad49)") (class "Default")
      (node (ref "JM1") (pin "49") (pinfunction "49_49") (pintype "passive"))
    )
    (net (code "164") (name "unconnected-(JM1-Pad50)") (class "Default")
      (node (ref "JM1") (pin "50") (pinfunction "50_50") (pintype "passive"))
    )
    (net (code "165") (name "unconnected-(JM1-Pad51)") (class "Default")
      (node (ref "JM1") (pin "51") (pinfunction "51_51") (pintype "passive"))
    )
    (net (code "166") (name "unconnected-(JM1-Pad52)") (class "Default")
      (node (ref "JM1") (pin "52") (pinfunction "52_52") (pintype "passive"))
    )
    (net (code "167") (name "unconnected-(JM1-Pad56)") (class "Default")
      (node (ref "JM1") (pin "56") (pinfunction "56_56") (pintype "passive"))
    )
    (net (code "168") (name "unconnected-(JM1-Pad58)") (class "Default")
      (node (ref "JM1") (pin "58") (pinfunction "58_58") (pintype "passive"))
    )
    (net (code "169") (name "unconnected-(JM1-Pad66)") (class "Default")
      (node (ref "JM1") (pin "66") (pinfunction "66_66") (pintype "passive"))
    )
    (net (code "170") (name "unconnected-(JM1-Pad68)") (class "Default")
      (node (ref "JM1") (pin "68") (pinfunction "68_68") (pintype "passive"))
    )
    (net (code "171") (name "unconnected-(JM1-Pad70)") (class "Default")
      (node (ref "JM1") (pin "70") (pinfunction "70_70") (pintype "passive"))
    )
    (net (code "172") (name "unconnected-(JM1-Pad72)") (class "Default")
      (node (ref "JM1") (pin "72") (pinfunction "72_72") (pintype "passive"))
    )
    (net (code "173") (name "unconnected-(JM1-Pad75)") (class "Default")
      (node (ref "JM1") (pin "75") (pinfunction "75_75") (pintype "passive"))
    )
    (net (code "174") (name "unconnected-(JM1-Pad77)") (class "Default")
      (node (ref "JM1") (pin "77") (pinfunction "77_77") (pintype "passive"))
    )
    (net (code "175") (name "unconnected-(JM1-Pad80)") (class "Default")
      (node (ref "JM1") (pin "80") (pinfunction "80_80") (pintype "passive"))
    )
    (net (code "176") (name "unconnected-(JM1-Pad82)") (class "Default")
      (node (ref "JM1") (pin "82") (pinfunction "82_82") (pintype "passive"))
    )
    (net (code "177") (name "unconnected-(JM1-Pad84)") (class "Default")
      (node (ref "JM1") (pin "84") (pinfunction "84_84") (pintype "passive"))
    )
    (net (code "178") (name "unconnected-(JM1-Pad86)") (class "Default")
      (node (ref "JM1") (pin "86") (pinfunction "86_86") (pintype "passive"))
    )
    (net (code "179") (name "unconnected-(JM1-Pad88)") (class "Default")
      (node (ref "JM1") (pin "88") (pinfunction "88_88") (pintype "passive"))
    )
    (net (code "180") (name "unconnected-(JM1-Pad90)") (class "Default")
      (node (ref "JM1") (pin "90") (pinfunction "90_90") (pintype "passive"))
    )
    (net (code "181") (name "unconnected-(JM1-Pad91)") (class "Default")
      (node (ref "JM1") (pin "91") (pinfunction "91_91") (pintype "passive"))
    )
    (net (code "182") (name "unconnected-(JM1-Pad92)") (class "Default")
      (node (ref "JM1") (pin "92") (pinfunction "92_92") (pintype "passive"))
    )
    (net (code "183") (name "unconnected-(JM1-Pad98)") (class "Default")
      (node (ref "JM1") (pin "98") (pinfunction "98_98") (pintype "passive"))
    )
    (net (code "184") (name "unconnected-(JM1-Pad100)") (class "Default")
      (node (ref "JM1") (pin "100") (pinfunction "100_100") (pintype "passive"))
    )
    (net (code "185") (name "unconnected-(JM2-Pad6)") (class "Default")
      (node (ref "JM2") (pin "6") (pinfunction "6_6") (pintype "passive+no_connect"))
    )
    (net (code "186") (name "unconnected-(JM2-Pad9)") (class "Default")
      (node (ref "JM2") (pin "9") (pinfunction "9_9") (pintype "passive"))
    )
    (net (code "187") (name "unconnected-(JM2-Pad11)") (class "Default")
      (node (ref "JM2") (pin "11") (pinfunction "11_11") (pintype "passive"))
    )
    (net (code "188") (name "unconnected-(JM2-Pad12)") (class "Default")
      (node (ref "JM2") (pin "12") (pinfunction "12_12") (pintype "passive"))
    )
    (net (code "189") (name "unconnected-(JM2-Pad13)") (class "Default")
      (node (ref "JM2") (pin "13") (pinfunction "13_13") (pintype "passive"))
    )
    (net (code "190") (name "unconnected-(JM2-Pad14)") (class "Default")
      (node (ref "JM2") (pin "14") (pinfunction "14_14") (pintype "passive"))
    )
    (net (code "191") (name "unconnected-(JM2-Pad15)") (class "Default")
      (node (ref "JM2") (pin "15") (pinfunction "15_15") (pintype "passive"))
    )
    (net (code "192") (name "unconnected-(JM2-Pad16)") (class "Default")
      (node (ref "JM2") (pin "16") (pinfunction "16_16") (pintype "passive"))
    )
    (net (code "193") (name "unconnected-(JM2-Pad17)") (class "Default")
      (node (ref "JM2") (pin "17") (pinfunction "17_17") (pintype "passive"))
    )
    (net (code "194") (name "unconnected-(JM2-Pad18)") (class "Default")
      (node (ref "JM2") (pin "18") (pinfunction "18_18") (pintype "passive"))
    )
    (net (code "195") (name "unconnected-(JM2-Pad20)") (class "Default")
      (node (ref "JM2") (pin "20") (pinfunction "20_20") (pintype "passive"))
    )
    (net (code "196") (name "unconnected-(JM2-Pad21)") (class "Default")
      (node (ref "JM2") (pin "21") (pinfunction "21_21") (pintype "passive"))
    )
    (net (code "197") (name "unconnected-(JM2-Pad22)") (class "Default")
      (node (ref "JM2") (pin "22") (pinfunction "22_22") (pintype "passive"))
    )
    (net (code "198") (name "unconnected-(JM2-Pad23)") (class "Default")
      (node (ref "JM2") (pin "23") (pinfunction "23_23") (pintype "passive"))
    )
    (net (code "199") (name "unconnected-(JM2-Pad24)") (class "Default")
      (node (ref "JM2") (pin "24") (pinfunction "24_24") (pintype "passive"))
    )
    (net (code "200") (name "unconnected-(JM2-Pad25)") (class "Default")
      (node (ref "JM2") (pin "25") (pinfunction "25_25") (pintype "passive"))
    )
    (net (code "201") (name "unconnected-(JM2-Pad26)") (class "Default")
      (node (ref "JM2") (pin "26") (pinfunction "26_26") (pintype "passive"))
    )
    (net (code "202") (name "unconnected-(JM2-Pad27)") (class "Default")
      (node (ref "JM2") (pin "27") (pinfunction "27_27") (pintype "passive"))
    )
    (net (code "203") (name "unconnected-(JM2-Pad28)") (class "Default")
      (node (ref "JM2") (pin "28") (pinfunction "28_28") (pintype "passive"))
    )
    (net (code "204") (name "unconnected-(JM2-Pad30)") (class "Default")
      (node (ref "JM2") (pin "30") (pinfunction "30_30") (pintype "passive+no_connect"))
    )
    (net (code "205") (name "unconnected-(JM2-Pad32)") (class "Default")
      (node (ref "JM2") (pin "32") (pinfunction "32_32") (pintype "passive"))
    )
    (net (code "206") (name "unconnected-(JM2-Pad34)") (class "Default")
      (node (ref "JM2") (pin "34") (pinfunction "34_34") (pintype "passive"))
    )
    (net (code "207") (name "unconnected-(JM2-Pad36)") (class "Default")
      (node (ref "JM2") (pin "36") (pinfunction "36_36") (pintype "passive"))
    )
    (net (code "208") (name "unconnected-(JM2-Pad38)") (class "Default")
      (node (ref "JM2") (pin "38") (pinfunction "38_38") (pintype "passive"))
    )
    (net (code "209") (name "unconnected-(JM2-Pad67)") (class "Default")
      (node (ref "JM2") (pin "67") (pinfunction "67_67") (pintype "passive"))
    )
    (net (code "210") (name "unconnected-(JM2-Pad71)") (class "Default")
      (node (ref "JM2") (pin "71") (pinfunction "71_71") (pintype "passive"))
    )
    (net (code "211") (name "unconnected-(JM2-Pad72)") (class "Default")
      (node (ref "JM2") (pin "72") (pinfunction "72_72") (pintype "passive"))
    )
    (net (code "212") (name "unconnected-(JM2-Pad73)") (class "Default")
      (node (ref "JM2") (pin "73") (pinfunction "73_73") (pintype "passive"))
    )
    (net (code "213") (name "unconnected-(JM2-Pad74)") (class "Default")
      (node (ref "JM2") (pin "74") (pinfunction "74_74") (pintype "passive"))
    )
    (net (code "214") (name "unconnected-(JM2-Pad75)") (class "Default")
      (node (ref "JM2") (pin "75") (pinfunction "75_75") (pintype "passive"))
    )
    (net (code "215") (name "unconnected-(JM2-Pad76)") (class "Default")
      (node (ref "JM2") (pin "76") (pinfunction "76_76") (pintype "passive"))
    )
    (net (code "216") (name "unconnected-(JM2-Pad77)") (class "Default")
      (node (ref "JM2") (pin "77") (pinfunction "77_77") (pintype "passive"))
    )
    (net (code "217") (name "unconnected-(JM2-Pad78)") (class "Default")
      (node (ref "JM2") (pin "78") (pinfunction "78_78") (pintype "passive"))
    )
    (net (code "218") (name "unconnected-(JM2-Pad81)") (class "Default")
      (node (ref "JM2") (pin "81") (pinfunction "81_81") (pintype "passive"))
    )
    (net (code "219") (name "unconnected-(JM2-Pad82)") (class "Default")
      (node (ref "JM2") (pin "82") (pinfunction "82_82") (pintype "passive"))
    )
    (net (code "220") (name "unconnected-(JM2-Pad83)") (class "Default")
      (node (ref "JM2") (pin "83") (pinfunction "83_83") (pintype "passive"))
    )
    (net (code "221") (name "unconnected-(JM2-Pad84)") (class "Default")
      (node (ref "JM2") (pin "84") (pinfunction "84_84") (pintype "passive"))
    )
    (net (code "222") (name "unconnected-(JM2-Pad85)") (class "Default")
      (node (ref "JM2") (pin "85") (pinfunction "85_85") (pintype "passive"))
    )
    (net (code "223") (name "unconnected-(JM2-Pad86)") (class "Default")
      (node (ref "JM2") (pin "86") (pinfunction "86_86") (pintype "passive"))
    )
    (net (code "224") (name "unconnected-(JM2-Pad87)") (class "Default")
      (node (ref "JM2") (pin "87") (pinfunction "87_87") (pintype "passive"))
    )
    (net (code "225") (name "unconnected-(JM2-Pad88)") (class "Default")
      (node (ref "JM2") (pin "88") (pinfunction "88_88") (pintype "passive"))
    )
    (net (code "226") (name "unconnected-(JM2-Pad90)") (class "Default")
      (node (ref "JM2") (pin "90") (pinfunction "90_90") (pintype "passive"))
    )
    (net (code "227") (name "unconnected-(JM2-Pad91)") (class "Default")
      (node (ref "JM2") (pin "91") (pinfunction "91_91") (pintype "passive"))
    )
    (net (code "228") (name "unconnected-(JM2-Pad93)") (class "Default")
      (node (ref "JM2") (pin "93") (pinfunction "93_93") (pintype "passive"))
    )
    (net (code "229") (name "unconnected-(JM2-Pad95)") (class "Default")
      (node (ref "JM2") (pin "95") (pinfunction "95_95") (pintype "passive"))
    )
    (net (code "230") (name "unconnected-(JM2-Pad97)") (class "Default")
      (node (ref "JM2") (pin "97") (pinfunction "97_97") (pintype "passive"))
    )
    (net (code "231") (name "unconnected-(JM2-Pad99)") (class "Default")
      (node (ref "JM2") (pin "99") (pinfunction "99_99") (pintype "passive"))
    )
    (net (code "232") (name "unconnected-(JM3-Pad1)") (class "Default")
      (node (ref "JM3") (pin "1") (pinfunction "1_1") (pintype "passive"))
    )
    (net (code "233") (name "unconnected-(JM3-Pad2)") (class "Default")
      (node (ref "JM3") (pin "2") (pinfunction "2_2") (pintype "passive"))
    )
    (net (code "234") (name "unconnected-(JM3-Pad3)") (class "Default")
      (node (ref "JM3") (pin "3") (pinfunction "3_3") (pintype "passive"))
    )
    (net (code "235") (name "unconnected-(JM3-Pad4)") (class "Default")
      (node (ref "JM3") (pin "4") (pinfunction "4_4") (pintype "passive"))
    )
    (net (code "236") (name "unconnected-(JM3-Pad31)") (class "Default")
      (node (ref "JM3") (pin "31") (pinfunction "31_31") (pintype "passive"))
    )
    (net (code "237") (name "unconnected-(JM3-Pad33)") (class "Default")
      (node (ref "JM3") (pin "33") (pinfunction "33_33") (pintype "passive"))
    )
    (net (code "238") (name "unconnected-(JM3-Pad37)") (class "Default")
      (node (ref "JM3") (pin "37") (pinfunction "37_37") (pintype "passive"))
    )
    (net (code "239") (name "unconnected-(JM3-Pad38)") (class "Default")
      (node (ref "JM3") (pin "38") (pinfunction "38_38") (pintype "passive"))
    )
    (net (code "240") (name "unconnected-(JM3-Pad39)") (class "Default")
      (node (ref "JM3") (pin "39") (pinfunction "39_39") (pintype "passive"))
    )
    (net (code "241") (name "unconnected-(JM3-Pad40)") (class "Default")
      (node (ref "JM3") (pin "40") (pinfunction "40_40") (pintype "passive"))
    )
    (net (code "242") (name "unconnected-(JM3-Pad41)") (class "Default")
      (node (ref "JM3") (pin "41") (pinfunction "41_41") (pintype "passive"))
    )
    (net (code "243") (name "unconnected-(JM3-Pad42)") (class "Default")
      (node (ref "JM3") (pin "42") (pinfunction "42_42") (pintype "passive"))
    )
    (net (code "244") (name "unconnected-(JM3-Pad43)") (class "Default")
      (node (ref "JM3") (pin "43") (pinfunction "43_43") (pintype "passive"))
    )
    (net (code "245") (name "unconnected-(JM3-Pad44)") (class "Default")
      (node (ref "JM3") (pin "44") (pinfunction "44_44") (pintype "passive"))
    )
    (net (code "246") (name "unconnected-(JM3-Pad47)") (class "Default")
      (node (ref "JM3") (pin "47") (pinfunction "47_47") (pintype "passive"))
    )
    (net (code "247") (name "unconnected-(JM3-Pad48)") (class "Default")
      (node (ref "JM3") (pin "48") (pinfunction "48_48") (pintype "passive"))
    )
    (net (code "248") (name "unconnected-(JM3-Pad49)") (class "Default")
      (node (ref "JM3") (pin "49") (pinfunction "49_49") (pintype "passive"))
    )
    (net (code "249") (name "unconnected-(JM3-Pad50)") (class "Default")
      (node (ref "JM3") (pin "50") (pinfunction "50_50") (pintype "passive"))
    )
    (net (code "250") (name "unconnected-(JM3-Pad51)") (class "Default")
      (node (ref "JM3") (pin "51") (pinfunction "51_51") (pintype "passive"))
    )
    (net (code "251") (name "unconnected-(JM3-Pad52)") (class "Default")
      (node (ref "JM3") (pin "52") (pinfunction "52_52") (pintype "passive"))
    )
    (net (code "252") (name "unconnected-(JM3-Pad53)") (class "Default")
      (node (ref "JM3") (pin "53") (pinfunction "53_53") (pintype "passive"))
    )
    (net (code "253") (name "unconnected-(JM3-Pad54)") (class "Default")
      (node (ref "JM3") (pin "54") (pinfunction "54_54") (pintype "passive"))
    )
    (net (code "254") (name "unconnected-(JM3-Pad55)") (class "Default")
      (node (ref "JM3") (pin "55") (pinfunction "55_55") (pintype "passive"))
    )
    (net (code "255") (name "unconnected-(JM3-Pad56)") (class "Default")
      (node (ref "JM3") (pin "56") (pinfunction "56_56") (pintype "passive"))
    )
    (net (code "256") (name "unconnected-(JM3-Pad57)") (class "Default")
      (node (ref "JM3") (pin "57") (pinfunction "57_57") (pintype "passive"))
    )
    (net (code "257") (name "unconnected-(JM3-Pad58)") (class "Default")
      (node (ref "JM3") (pin "58") (pinfunction "58_58") (pintype "passive"))
    )
    (net (code "258") (name "unconnected-(JM3-Pad59)") (class "Default")
      (node (ref "JM3") (pin "59") (pinfunction "59_59") (pintype "passive"))
    )
  )
)
